# bargraph_power_supply.net
KiCad netlist of a schematic drawn in EAGLE
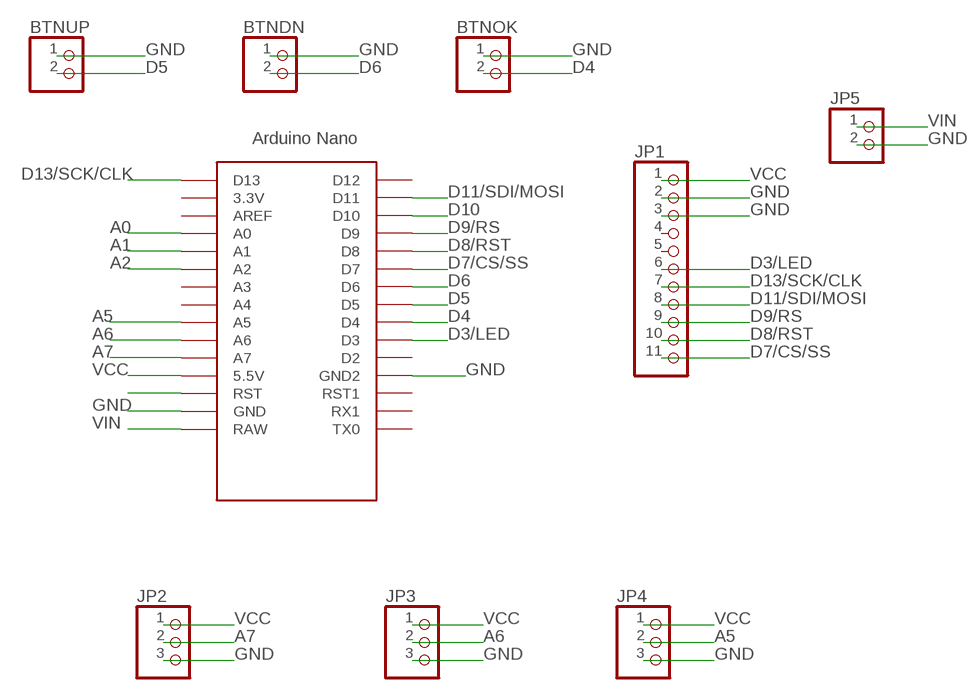
[diagram p0: schematic, sheet 1]

(export (version "E")
  (design (tool "Eeschema 10.0.6"))
  (components
    (comp (ref "BTNDN")
      (value "PINHD-1X2")
      (footprint "eagle-import:1X02")
      (libsource (lib "eagle-import") (part "PINHD-1X2"))
    )
    (comp (ref "BTNOK")
      (value "PINHD-1X2")
      (footprint "eagle-import:1X02")
      (libsource (lib "eagle-import") (part "PINHD-1X2"))
    )
    (comp (ref "BTNUP")
      (value "PINHD-1X2")
      (footprint "eagle-import:1X02")
      (libsource (lib "eagle-import") (part "PINHD-1X2"))
    )
    (comp (ref "JP1")
      (value "PINHD-1X11")
      (footprint "eagle-import:1X11")
      (libsource (lib "eagle-import") (part "PINHD-1X11"))
    )
    (comp (ref "JP2")
      (value "PINHD-1X3")
      (footprint "eagle-import:1X03")
      (libsource (lib "eagle-import") (part "PINHD-1X3"))
    )
    (comp (ref "JP3")
      (value "PINHD-1X3")
      (footprint "eagle-import:1X03")
      (libsource (lib "eagle-import") (part "PINHD-1X3"))
    )
    (comp (ref "JP4")
      (value "PINHD-1X3")
      (footprint "eagle-import:1X03")
      (libsource (lib "eagle-import") (part "PINHD-1X3"))
    )
    (comp (ref "JP5")
      (value "PINHD-1X2")
      (footprint "eagle-import:1X02")
      (libsource (lib "eagle-import") (part "PINHD-1X2"))
    )
    (comp (ref "U$1")
      (value "NANO")
      (footprint "eagle-import:NANO")
      (libsource (lib "eagle-import") (part "NANO"))
    )
  )
  (nets
    (net (code "1") (name "/A0") (class "Default")
      (node (ref "U$1") (pin "A0") (pinfunction "A0_A0") (pintype "bidirectional"))
    )
    (net (code "2") (name "/A1") (class "Default")
      (node (ref "U$1") (pin "A1") (pinfunction "A1_A1") (pintype "bidirectional"))
    )
    (net (code "3") (name "/A2") (class "Default")
      (node (ref "U$1") (pin "A2") (pinfunction "A2_A2") (pintype "bidirectional"))
    )
    (net (code "4") (name "/A5") (class "Default")
      (node (ref "JP4") (pin "2") (pinfunction "2_2") (pintype "passive"))
      (node (ref "U$1") (pin "A5") (pinfunction "A5_A5") (pintype "bidirectional"))
    )
    (net (code "5") (name "/A6") (class "Default")
      (node (ref "JP3") (pin "2") (pinfunction "2_2") (pintype "passive"))
      (node (ref "U$1") (pin "A6") (pinfunction "A6_A6") (pintype "bidirectional"))
    )
    (net (code "6") (name "/A7") (class "Default")
      (node (ref "JP2") (pin "2") (pinfunction "2_2") (pintype "passive"))
      (node (ref "U$1") (pin "A7") (pinfunction "A7_A7") (pintype "bidirectional"))
    )
    (net (code "7") (name "/D3{slash}LED") (class "Default")
      (node (ref "JP1") (pin "6") (pinfunction "6_6") (pintype "passive"))
      (node (ref "U$1") (pin "D3") (pinfunction "D3_D3") (pintype "bidirectional"))
    )
    (net (code "8") (name "/D4") (class "Default")
      (node (ref "BTNOK") (pin "2") (pinfunction "2_2") (pintype "passive"))
      (node (ref "U$1") (pin "D4") (pinfunction "D4_D4") (pintype "bidirectional"))
    )
    (net (code "9") (name "/D5") (class "Default")
      (node (ref "BTNUP") (pin "2") (pinfunction "2_2") (pintype "passive"))
      (node (ref "U$1") (pin "D5") (pinfunction "D5_D5") (pintype "bidirectional"))
    )
    (net (code "10") (name "/D6") (class "Default")
      (node (ref "BTNDN") (pin "2") (pinfunction "2_2") (pintype "passive"))
      (node (ref "U$1") (pin "D6") (pinfunction "D6_D6") (pintype "bidirectional"))
    )
    (net (code "11") (name "/D7{slash}CS{slash}SS") (class "Default")
      (node (ref "JP1") (pin "11") (pinfunction "11_11") (pintype "passive"))
      (node (ref "U$1") (pin "D7") (pinfunction "D7_D7") (pintype "bidirectional"))
    )
    (net (code "12") (name "/D8{slash}RST") (class "Default")
      (node (ref "JP1") (pin "10") (pinfunction "10_10") (pintype "passive"))
      (node (ref "U$1") (pin "D8") (pinfunction "D8_D8") (pintype "bidirectional"))
    )
    (net (code "13") (name "/D9{slash}RS") (class "Default")
      (node (ref "JP1") (pin "9") (pinfunction "9_9") (pintype "passive"))
      (node (ref "U$1") (pin "D9") (pinfunction "D9_D9") (pintype "bidirectional"))
    )
    (net (code "14") (name "/D10") (class "Default")
      (node (ref "U$1") (pin "D10") (pinfunction "D10_D10") (pintype "bidirectional"))
    )
    (net (code "15") (name "/D11{slash}SDI{slash}MOSI") (class "Default")
      (node (ref "JP1") (pin "8") (pinfunction "8_8") (pintype "passive"))
      (node (ref "U$1") (pin "D11") (pinfunction "D11_D11") (pintype "bidirectional"))
    )
    (net (code "16") (name "/D13{slash}SCK{slash}CLK") (class "Default")
      (node (ref "JP1") (pin "7") (pinfunction "7_7") (pintype "passive"))
      (node (ref "U$1") (pin "D13") (pinfunction "D13_D13") (pintype "bidirectional"))
    )
    (net (code "17") (name "/GND") (class "Default")
      (node (ref "BTNDN") (pin "1") (pinfunction "1_1") (pintype "passive"))
      (node (ref "BTNOK") (pin "1") (pinfunction "1_1") (pintype "passive"))
      (node (ref "BTNUP") (pin "1") (pinfunction "1_1") (pintype "passive"))
      (node (ref "JP1") (pin "2") (pinfunction "2_2") (pintype "passive"))
      (node (ref "JP1") (pin "3") (pinfunction "3_3") (pintype "passive"))
      (node (ref "JP2") (pin "3") (pinfunction "3_3") (pintype "passive"))
      (node (ref "JP3") (pin "3") (pinfunction "3_3") (pintype "passive"))
      (node (ref "JP4") (pin "3") (pinfunction "3_3") (pintype "passive"))
      (node (ref "JP5") (pin "2") (pinfunction "2_2") (pintype "passive"))
      (node (ref "U$1") (pin "GND") (pinfunction "GND_GND") (pintype "bidirectional"))
      (node (ref "U$1") (pin "GND1") (pinfunction "GND2_GND1") (pintype "bidirectional"))
    )
    (net (code "18") (name "/VCC") (class "Default")
      (node (ref "JP1") (pin "1") (pinfunction "1_1") (pintype "passive"))
      (node (ref "JP2") (pin "1") (pinfunction "1_1") (pintype "passive"))
      (node (ref "JP3") (pin "1") (pinfunction "1_1") (pintype "passive"))
      (node (ref "JP4") (pin "1") (pinfunction "1_1") (pintype "passive"))
      (node (ref "U$1") (pin "5V") (pinfunction "5.5V_5V") (pintype "bidirectional"))
    )
    (net (code "19") (name "/VIN") (class "Default")
      (node (ref "JP5") (pin "1") (pinfunction "1_1") (pintype "passive"))
      (node (ref "U$1") (pin "RAW") (pinfunction "RAW_RAW") (pintype "bidirectional"))
    )
    (net (code "20") (name "unconnected-(JP1-Pad4)") (class "Default")
      (node (ref "JP1") (pin "4") (pinfunction "4_4") (pintype "passive"))
    )
    (net (code "21") (name "unconnected-(JP1-Pad5)") (class "Default")
      (node (ref "JP1") (pin "5") (pinfunction "5_5") (pintype "passive"))
    )
    (net (code "22") (name "unconnected-(U$1-Pad3.3V)") (class "Default")
      (node (ref "U$1") (pin "3.3V") (pinfunction "3.3V_3.3V") (pintype "bidirectional"))
    )
    (net (code "23") (name "unconnected-(U$1-PadA3)") (class "Default")
      (node (ref "U$1") (pin "A3") (pinfunction "A3_A3") (pintype "bidirectional"))
    )
    (net (code "24") (name "unconnected-(U$1-PadA4)") (class "Default")
      (node (ref "U$1") (pin "A4") (pinfunction "A4_A4") (pintype "bidirectional"))
    )
    (net (code "25") (name "unconnected-(U$1-PadAREF)") (class "Default")
      (node (ref "U$1") (pin "AREF") (pinfunction "AREF_AREF") (pintype "bidirectional"))
    )
    (net (code "26") (name "unconnected-(U$1-PadD2)") (class "Default")
      (node (ref "U$1") (pin "D2") (pinfunction "D2_D2") (pintype "bidirectional"))
    )
    (net (code "27") (name "unconnected-(U$1-PadD12)") (class "Default")
      (node (ref "U$1") (pin "D12") (pinfunction "D12_D12") (pintype "bidirectional"))
    )
    (net (code "28") (name "unconnected-(U$1-PadICSP1)") (class "Default")
      (node (ref "U$1") (pin "ICSP1") (pinfunction "ICSP1_ICSP1") (pintype "bidirectional"))
    )
    (net (code "29") (name "unconnected-(U$1-PadICSP2)") (class "Default")
      (node (ref "U$1") (pin "ICSP2") (pinfunction "ICSP2_ICSP2") (pintype "bidirectional"))
    )
    (net (code "30") (name "unconnected-(U$1-PadICSP3)") (class "Default")
      (node (ref "U$1") (pin "ICSP3") (pinfunction "ICSP3_ICSP3") (pintype "bidirectional"))
    )
    (net (code "31") (name "unconnected-(U$1-PadICSP4)") (class "Default")
      (node (ref "U$1") (pin "ICSP4") (pinfunction "ICSP4_ICSP4") (pintype "bidirectional"))
    )
    (net (code "32") (name "unconnected-(U$1-PadICSP5)") (class "Default")
      (node (ref "U$1") (pin "ICSP5") (pinfunction "ICSP5_ICSP5") (pintype "bidirectional"))
    )
    (net (code "33") (name "unconnected-(U$1-PadICSP6)") (class "Default")
      (node (ref "U$1") (pin "ICSP6") (pinfunction "ICSP6_ICSP6") (pintype "bidirectional"))
    )
    (net (code "34") (name "unconnected-(U$1-PadRST)") (class "Default")
      (node (ref "U$1") (pin "RST") (pinfunction "RST_RST") (pintype "bidirectional"))
    )
    (net (code "35") (name "unconnected-(U$1-PadRST1)") (class "Default")
      (node (ref "U$1") (pin "RST1") (pinfunction "RST1_RST1") (pintype "bidirectional"))
    )
    (net (code "36") (name "unconnected-(U$1-PadRX1)") (class "Default")
      (node (ref "U$1") (pin "RX1") (pinfunction "RX1_RX1") (pintype "bidirectional"))
    )
    (net (code "37") (name "unconnected-(U$1-PadTX0)") (class "Default")
      (node (ref "U$1") (pin "TX0") (pinfunction "TX0_TX0") (pintype "bidirectional"))
    )
  )
)
